# SFP_10GbE_Port0.net
KiCad netlist of a schematic drawn in Altium Designer
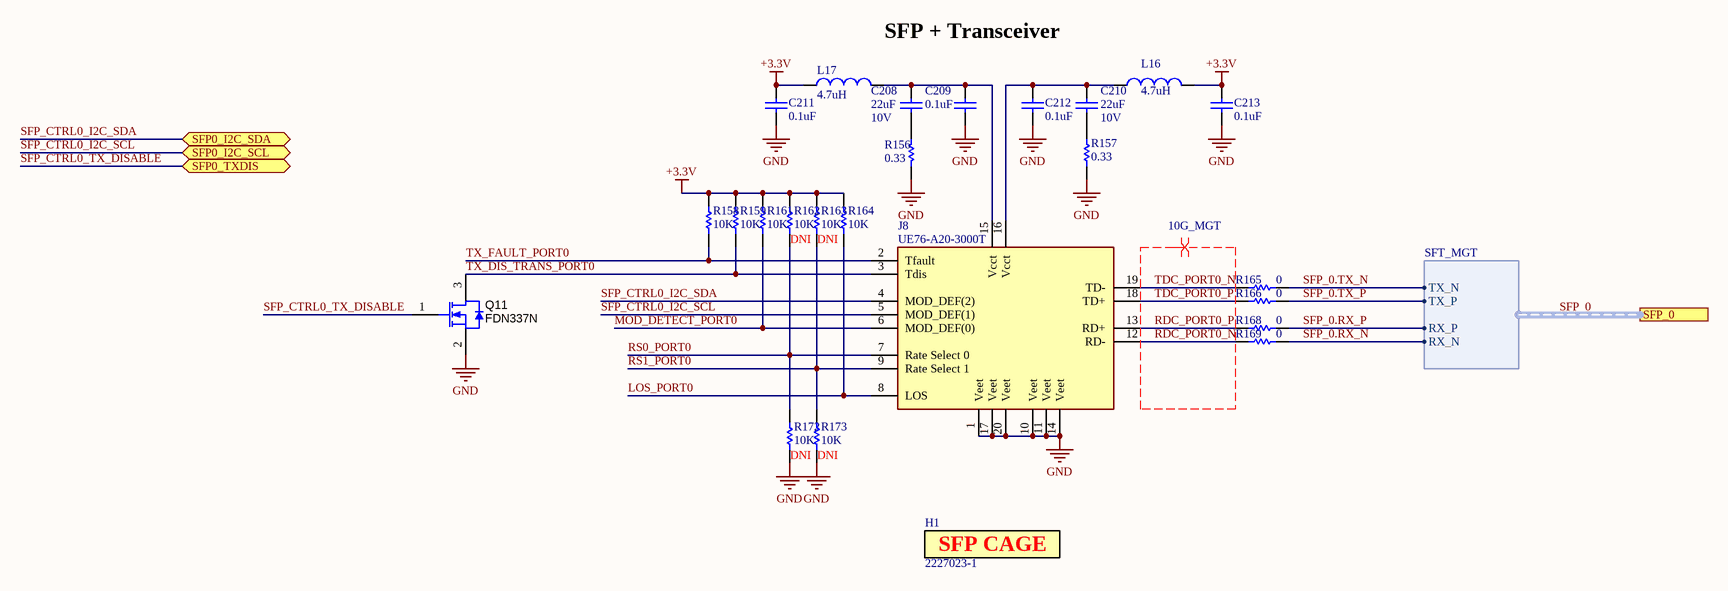
[diagram p0: SFP_10GbE_Port0.SchDoc]

(export (version "E")
  (design (tool "Eeschema 10.0.6"))
  (components
    (comp (ref "C208")
      (value "22uF")
      (footprint "CAPC1608X100N")
      (description "Multilayer Ceramic Capacitor, 22 uF, 10 V, ± 20%, X5R, 0603 [1608 Metric]")
      (fields
        (field (name "MANUFACTURER") "TDK")
        (field (name "MANUFACTURER PART NUMBER") "C1608X5R1A226M080AC")
        (field (name "VOLTAGE RATING") "10V")
      )
      (libsource (lib "Radar FPGA RF") (part "CAP CER 22UF 10V X5R 0603"))
    )
    (comp (ref "C209")
      (value "0.1uF")
      (footprint "CAPC1005X55USR")
      (description "CAP CER 0.1UF 25V X5R 0402")
      (fields
        (field (name "MANUFACTURER PART NUMBER") "CL05A104KA5NNNC")
        (field (name "MANUFACTURER") "Samsung Electro-Mechanics")
      )
      (libsource (lib "Radar FPGA RF") (part "CAP CER 0.1UF 25V X5R 0402"))
    )
    (comp (ref "C210")
      (value "22uF")
      (footprint "CAPC1608X100N")
      (description "Multilayer Ceramic Capacitor, 22 uF, 10 V, ± 20%, X5R, 0603 [1608 Metric]")
      (fields
        (field (name "MANUFACTURER") "TDK")
        (field (name "MANUFACTURER PART NUMBER") "C1608X5R1A226M080AC")
        (field (name "VOLTAGE RATING") "10V")
      )
      (libsource (lib "Radar FPGA RF") (part "CAP CER 22UF 10V X5R 0603"))
    )
    (comp (ref "C211")
      (value "0.1uF")
      (footprint "CAPC1005X55USR")
      (description "CAP CER 0.1UF 25V X5R 0402")
      (fields
        (field (name "MANUFACTURER PART NUMBER") "CL05A104KA5NNNC")
        (field (name "MANUFACTURER") "Samsung Electro-Mechanics")
      )
      (libsource (lib "Radar FPGA RF") (part "CAP CER 0.1UF 25V X5R 0402"))
    )
    (comp (ref "C212")
      (value "0.1uF")
      (footprint "CAPC1005X55USR")
      (description "CAP CER 0.1UF 25V X5R 0402")
      (fields
        (field (name "MANUFACTURER PART NUMBER") "CL05A104KA5NNNC")
        (field (name "MANUFACTURER") "Samsung Electro-Mechanics")
      )
      (libsource (lib "Radar FPGA RF") (part "CAP CER 0.1UF 25V X5R 0402"))
    )
    (comp (ref "C213")
      (value "0.1uF")
      (footprint "CAPC1005X55USR")
      (description "CAP CER 0.1UF 25V X5R 0402")
      (fields
        (field (name "MANUFACTURER PART NUMBER") "CL05A104KA5NNNC")
        (field (name "MANUFACTURER") "Samsung Electro-Mechanics")
      )
      (libsource (lib "Radar FPGA RF") (part "CAP CER 0.1UF 25V X5R 0402"))
    )
    (comp (ref "H1")
      (value "2227023-1")
      (footprint "TE_2227023-1")
      (description "Connector Accessories 1 Port SFP Cage Press Fit Right Angle Through Hole Nickel Tray")
      (fields (field (name "MANUFACTURER") "TE Connectivity AMP"))
      (libsource (lib "XEM8320") (part "TE_2227023-1"))
    )
    (comp (ref "J8")
      (value "UE76-A20-3000T")
      (footprint "AMPHENOL_UE76-A20-3000T")
      (description "Conn SFP+ RCP 20 POS 0.8mm Solder RA SMD 20 Terminal 1 Port T/R")
      (fields (field (name "MANUFACTURER") "Amphenol Communications Solutions"))
      (libsource (lib "Radar FPGA RF") (part "UE76-A20-3000T"))
    )
    (comp (ref "L16")
      (value "4.7uH")
      (footprint "DFE252012P")
      (description "FIXED IND 4.7UH 2A 200 MOHM SMD")
      (fields
        (field (name "MANUFACTURER") "Murata")
        (field (name "MANUFACTURER PART NUMBER") "DFE252012P-4R7M=P2")
      )
      (libsource (lib "") (part "FIXED IND 4.7UH 2A 200 MOHM SMD_1"))
    )
    (comp (ref "L17")
      (value "4.7uH")
      (footprint "DFE252012P")
      (description "FIXED IND 4.7UH 2A 200 MOHM SMD")
      (fields
        (field (name "MANUFACTURER") "Murata")
        (field (name "MANUFACTURER PART NUMBER") "DFE252012P-4R7M=P2")
      )
      (libsource (lib "Radar FPGA RF") (part "FIXED IND 4.7UH 2A 200 MOHM SMD"))
    )
    (comp (ref "Q11")
      (value "FDN337N")
      (footprint "SOT-23")
      (description "MOSFET N-CH 30V 2.2A SSOT3")
      (fields (field (name "MANUFACTURER") "ON Semiconductor / Fairchild"))
      (libsource (lib "Radar FPGA RF") (part "MOSFET N-CH 30V 2.2A SUPERSOT3"))
    )
    (comp (ref "R156")
      (value "0.33")
      (footprint "RESC1608X55N")
      (description "RES 0.33 OHM 1% 1/10W 0603")
      (fields
        (field (name "MANUFACTURER") "Panasonic Electronic Components")
        (field (name "MANUFACTURER PART NUMBER") "ERJ-3RQFR33V")
      )
      (libsource (lib "Radar FPGA RF") (part "RES 0.33 OHM 1% 1/10W 0603"))
    )
    (comp (ref "R157")
      (value "0.33")
      (footprint "RESC1608X55N")
      (description "RES 0.33 OHM 1% 1/10W 0603")
      (fields
        (field (name "MANUFACTURER") "Panasonic Electronic Components")
        (field (name "MANUFACTURER PART NUMBER") "ERJ-3RQFR33V")
      )
      (libsource (lib "Radar FPGA RF") (part "RES 0.33 OHM 1% 1/10W 0603"))
    )
    (comp (ref "R158")
      (value "10K")
      (footprint "RESC1005X40USR")
      (description "RES 10K OHM 1% 1/16W 0402")
      (fields
        (field (name "MANUFACTURER") "YAGEO")
        (field (name "MANUFACTURER PART NUMBER") "RC0402FR-0710KL")
      )
      (libsource (lib "Radar FPGA RF") (part "RES 10K OHM 1% 1/16W 0402"))
    )
    (comp (ref "R159")
      (value "10K")
      (footprint "RESC1005X40USR")
      (description "RES 10K OHM 1% 1/16W 0402")
      (fields
        (field (name "MANUFACTURER") "YAGEO")
        (field (name "MANUFACTURER PART NUMBER") "RC0402FR-0710KL")
      )
      (libsource (lib "Radar FPGA RF") (part "RES 10K OHM 1% 1/16W 0402"))
    )
    (comp (ref "R161")
      (value "10K")
      (footprint "RESC1005X40USR")
      (description "RES 10K OHM 1% 1/16W 0402")
      (fields
        (field (name "MANUFACTURER") "YAGEO")
        (field (name "MANUFACTURER PART NUMBER") "RC0402FR-0710KL")
      )
      (libsource (lib "Radar FPGA RF") (part "RES 10K OHM 1% 1/16W 0402"))
    )
    (comp (ref "R162")
      (value "10K")
      (footprint "RESC1005X40USR")
      (description "RES 10K OHM 1% 1/16W 0402")
      (fields
        (field (name "MANUFACTURER") "YAGEO")
        (field (name "MANUFACTURER PART NUMBER") "RC0402FR-0710KL")
      )
      (libsource (lib "Radar FPGA RF") (part "RES 10K OHM 1% 1/16W 0402"))
    )
    (comp (ref "R163")
      (value "10K")
      (footprint "RESC1005X40USR")
      (description "RES 10K OHM 1% 1/16W 0402")
      (fields
        (field (name "MANUFACTURER") "YAGEO")
        (field (name "MANUFACTURER PART NUMBER") "RC0402FR-0710KL")
      )
      (libsource (lib "Radar FPGA RF") (part "RES 10K OHM 1% 1/16W 0402"))
    )
    (comp (ref "R164")
      (value "10K")
      (footprint "RESC1005X40USR")
      (description "RES 10K OHM 1% 1/16W 0402")
      (fields
        (field (name "MANUFACTURER") "YAGEO")
        (field (name "MANUFACTURER PART NUMBER") "RC0402FR-0710KL")
      )
      (libsource (lib "Radar FPGA RF") (part "RES 10K OHM 1% 1/16W 0402"))
    )
    (comp (ref "R165")
      (value "0")
      (footprint "RESC1005X40USR")
      (description "RES 0 OHM JUMPER 1/16W 0402")
      (fields
        (field (name "MANUFACTURER") "Yageo")
        (field (name "MANUFACTURER PART NUMBER") "RC0402JR-070RL")
      )
      (libsource (lib "Radar FPGA RF") (part "RES 0 OHM JUMPER 1/16W 0402"))
    )
    (comp (ref "R166")
      (value "0")
      (footprint "RESC1005X40USR")
      (description "RES 0 OHM JUMPER 1/16W 0402")
      (fields
        (field (name "MANUFACTURER") "Yageo")
        (field (name "MANUFACTURER PART NUMBER") "RC0402JR-070RL")
      )
      (libsource (lib "Radar FPGA RF") (part "RES 0 OHM JUMPER 1/16W 0402"))
    )
    (comp (ref "R168")
      (value "0")
      (footprint "RESC1005X40USR")
      (description "RES 0 OHM JUMPER 1/16W 0402")
      (fields
        (field (name "MANUFACTURER") "Yageo")
        (field (name "MANUFACTURER PART NUMBER") "RC0402JR-070RL")
      )
      (libsource (lib "Radar FPGA RF") (part "RES 0 OHM JUMPER 1/16W 0402"))
    )
    (comp (ref "R169")
      (value "0")
      (footprint "RESC1005X40USR")
      (description "RES 0 OHM JUMPER 1/16W 0402")
      (fields
        (field (name "MANUFACTURER") "Yageo")
        (field (name "MANUFACTURER PART NUMBER") "RC0402JR-070RL")
      )
      (libsource (lib "Radar FPGA RF") (part "RES 0 OHM JUMPER 1/16W 0402"))
    )
    (comp (ref "R172")
      (value "10K")
      (footprint "RESC1005X40USR")
      (description "RES 10K OHM 1% 1/16W 0402")
      (fields
        (field (name "MANUFACTURER") "YAGEO")
        (field (name "MANUFACTURER PART NUMBER") "RC0402FR-0710KL")
      )
      (libsource (lib "Radar FPGA RF") (part "RES 10K OHM 1% 1/16W 0402"))
    )
    (comp (ref "R173")
      (value "10K")
      (footprint "RESC1005X40USR")
      (description "RES 10K OHM 1% 1/16W 0402")
      (fields
        (field (name "MANUFACTURER") "YAGEO")
        (field (name "MANUFACTURER PART NUMBER") "RC0402FR-0710KL")
      )
      (libsource (lib "Radar FPGA RF") (part "RES 10K OHM 1% 1/16W 0402"))
    )
  )
  (nets
    (net (code "2") (name "+3.3V") (class "Default")
      (node (ref "C211") (pin "2") (pinfunction "2_2") (pintype "passive"))
      (node (ref "C213") (pin "2") (pinfunction "2_2") (pintype "passive"))
      (node (ref "L16") (pin "2") (pinfunction "2_2") (pintype "passive"))
      (node (ref "L17") (pin "2") (pinfunction "2_2") (pintype "passive"))
      (node (ref "R158") (pin "2") (pinfunction "2_2") (pintype "passive"))
      (node (ref "R159") (pin "2") (pinfunction "2_2") (pintype "passive"))
      (node (ref "R161") (pin "2") (pinfunction "2_2") (pintype "passive"))
      (node (ref "R162") (pin "2") (pinfunction "2_2") (pintype "passive"))
      (node (ref "R163") (pin "2") (pinfunction "2_2") (pintype "passive"))
      (node (ref "R164") (pin "2") (pinfunction "2_2") (pintype "passive"))
    )
    (net (code "3") (name "/LOS_PORT0") (class "Default")
      (node (ref "J8") (pin "8") (pinfunction "LOS_8") (pintype "passive"))
      (node (ref "R164") (pin "1") (pinfunction "1_1") (pintype "passive"))
    )
    (net (code "4") (name "/MOD_DETECT_PORT0") (class "Default")
      (node (ref "J8") (pin "6") (pinfunction "MOD_DEF(0)_6") (pintype "passive"))
      (node (ref "R161") (pin "1") (pinfunction "1_1") (pintype "passive"))
    )
    (net (code "5") (name "/RDC_PORT0_N") (class "Default")
      (node (ref "J8") (pin "12") (pinfunction "RD-_12") (pintype "passive"))
      (node (ref "R169") (pin "1") (pinfunction "1_1") (pintype "passive"))
    )
    (net (code "6") (name "/RDC_PORT0_P") (class "Default")
      (node (ref "J8") (pin "13") (pinfunction "RD+_13") (pintype "passive"))
      (node (ref "R168") (pin "1") (pinfunction "1_1") (pintype "passive"))
    )
    (net (code "7") (name "/RS0_PORT0") (class "Default")
      (node (ref "J8") (pin "7") (pinfunction "Rate_Select_0_7") (pintype "passive"))
      (node (ref "R162") (pin "1") (pinfunction "1_1") (pintype "passive"))
      (node (ref "R172") (pin "2") (pinfunction "2_2") (pintype "passive"))
    )
    (net (code "8") (name "/RS1_PORT0") (class "Default")
      (node (ref "J8") (pin "9") (pinfunction "Rate_Select_1_9") (pintype "passive"))
      (node (ref "R163") (pin "1") (pinfunction "1_1") (pintype "passive"))
      (node (ref "R173") (pin "2") (pinfunction "2_2") (pintype "passive"))
    )
    (net (code "9") (name "/SFP_0.RX_N") (class "Default")
      (node (ref "R169") (pin "2") (pinfunction "2_2") (pintype "passive"))
    )
    (net (code "10") (name "/SFP_0.RX_P") (class "Default")
      (node (ref "R168") (pin "2") (pinfunction "2_2") (pintype "passive"))
    )
    (net (code "11") (name "/SFP_0.TX_N") (class "Default")
      (node (ref "R165") (pin "2") (pinfunction "2_2") (pintype "passive"))
    )
    (net (code "12") (name "/SFP_0.TX_P") (class "Default")
      (node (ref "R166") (pin "2") (pinfunction "2_2") (pintype "passive"))
    )
    (net (code "14") (name "/SFP_CTRL0_I2C_SCL") (class "Default")
      (node (ref "J8") (pin "5") (pinfunction "MOD_DEF(1)_5") (pintype "passive"))
    )
    (net (code "15") (name "/SFP_CTRL0_I2C_SDA") (class "Default")
      (node (ref "J8") (pin "4") (pinfunction "MOD_DEF(2)_4") (pintype "passive"))
    )
    (net (code "16") (name "/SFP_CTRL0_TX_DISABLE") (class "Default")
      (node (ref "Q11") (pin "1") (pinfunction "G_1") (pintype "passive"))
    )
    (net (code "17") (name "/TDC_PORT0_N") (class "Default")
      (node (ref "J8") (pin "19") (pinfunction "TD-_19") (pintype "passive"))
      (node (ref "R165") (pin "1") (pinfunction "1_1") (pintype "passive"))
    )
    (net (code "18") (name "/TDC_PORT0_P") (class "Default")
      (node (ref "J8") (pin "18") (pinfunction "TD+_18") (pintype "passive"))
      (node (ref "R166") (pin "1") (pinfunction "1_1") (pintype "passive"))
    )
    (net (code "19") (name "/TX_DIS_TRANS_PORT0") (class "Default")
      (node (ref "J8") (pin "3") (pinfunction "Tdis_3") (pintype "passive"))
      (node (ref "Q11") (pin "3") (pinfunction "D_3") (pintype "passive"))
      (node (ref "R159") (pin "1") (pinfunction "1_1") (pintype "passive"))
    )
    (net (code "20") (name "/TX_FAULT_PORT0") (class "Default")
      (node (ref "J8") (pin "2") (pinfunction "Tfault_2") (pintype "passive"))
      (node (ref "R158") (pin "1") (pinfunction "1_1") (pintype "passive"))
    )
    (net (code "21") (name "GND") (class "Default")
      (node (ref "C209") (pin "1") (pinfunction "1_1") (pintype "passive"))
      (node (ref "C211") (pin "1") (pinfunction "1_1") (pintype "passive"))
      (node (ref "C212") (pin "1") (pinfunction "1_1") (pintype "passive"))
      (node (ref "C213") (pin "1") (pinfunction "1_1") (pintype "passive"))
      (node (ref "J8") (pin "1") (pinfunction "Veet_1") (pintype "passive"))
      (node (ref "J8") (pin "10") (pinfunction "Veet_10") (pintype "passive"))
      (node (ref "J8") (pin "11") (pinfunction "Veet_11") (pintype "passive"))
      (node (ref "J8") (pin "14") (pinfunction "Veet_14") (pintype "passive"))
      (node (ref "J8") (pin "17") (pinfunction "Veet_17") (pintype "passive"))
      (node (ref "J8") (pin "20") (pinfunction "Veet_20") (pintype "passive"))
      (node (ref "Q11") (pin "2") (pinfunction "S_2") (pintype "passive"))
      (node (ref "R156") (pin "1") (pinfunction "1_1") (pintype "passive"))
      (node (ref "R157") (pin "1") (pinfunction "1_1") (pintype "passive"))
      (node (ref "R172") (pin "1") (pinfunction "1_1") (pintype "passive"))
      (node (ref "R173") (pin "1") (pinfunction "1_1") (pintype "passive"))
    )
    (net (code "22") (name "Net-(C208-Pad1)") (class "Default")
      (node (ref "C208") (pin "1") (pinfunction "1_1") (pintype "passive"))
      (node (ref "C209") (pin "2") (pinfunction "2_2") (pintype "passive"))
      (node (ref "J8") (pin "15") (pinfunction "Vcct_15") (pintype "passive"))
      (node (ref "L17") (pin "1") (pinfunction "1_1") (pintype "passive"))
    )
    (net (code "23") (name "Net-(C208-Pad2)") (class "Default")
      (node (ref "C208") (pin "2") (pinfunction "2_2") (pintype "passive"))
      (node (ref "R156") (pin "2") (pinfunction "2_2") (pintype "passive"))
    )
    (net (code "24") (name "Net-(C210-Pad1)") (class "Default")
      (node (ref "C210") (pin "1") (pinfunction "1_1") (pintype "passive"))
      (node (ref "C212") (pin "2") (pinfunction "2_2") (pintype "passive"))
      (node (ref "J8") (pin "16") (pinfunction "Vcct_16") (pintype "passive"))
      (node (ref "L16") (pin "1") (pinfunction "1_1") (pintype "passive"))
    )
    (net (code "25") (name "Net-(C210-Pad2)") (class "Default")
      (node (ref "C210") (pin "2") (pinfunction "2_2") (pintype "passive"))
      (node (ref "R157") (pin "2") (pinfunction "2_2") (pintype "passive"))
    )
  )
)
